# booster.net
KiCad netlist of a schematic drawn in EAGLE
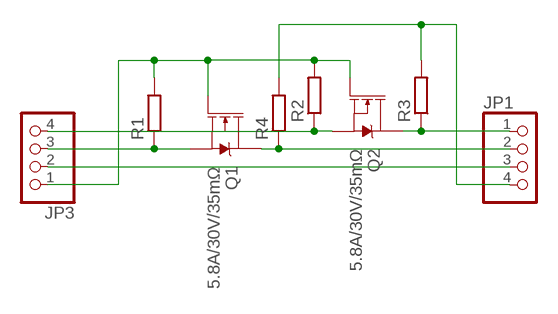
[diagram p0: schematic, sheet 1]

(export (version "E")
  (design (tool "Eeschema 10.0.6"))
  (components
    (comp (ref "JP1")
      (value "PINHD-1X4/90")
      (footprint "eagle-import:1X04_90")
      (libsource (lib "eagle-import") (part "PINHD-1X4/90"))
    )
    (comp (ref "JP3")
      (value "PINHD-1X4/90")
      (footprint "eagle-import:1X04_90")
      (libsource (lib "eagle-import") (part "PINHD-1X4/90"))
    )
    (comp (ref "Q1")
      (value "5.8A/30V/35mΩ")
      (footprint "eagle-import:SOT23-3")
      (libsource (lib "eagle-import") (part "MOSFET-NCH-AO3404A"))
    )
    (comp (ref "Q2")
      (value "5.8A/30V/35mΩ")
      (footprint "eagle-import:SOT23-3")
      (libsource (lib "eagle-import") (part "MOSFET-NCH-AO3404A"))
    )
    (comp (ref "R1")
      (value "R-EU_R0805")
      (footprint "eagle-import:R0805")
      (libsource (lib "eagle-import") (part "R-EU_R0805"))
    )
    (comp (ref "R2")
      (value "R-EU_R0805")
      (footprint "eagle-import:R0805")
      (libsource (lib "eagle-import") (part "R-EU_R0805"))
    )
    (comp (ref "R3")
      (value "R-EU_R0805")
      (footprint "eagle-import:R0805")
      (libsource (lib "eagle-import") (part "R-EU_R0805"))
    )
    (comp (ref "R4")
      (value "R-EU_R0805")
      (footprint "eagle-import:R0805")
      (libsource (lib "eagle-import") (part "R-EU_R0805"))
    )
  )
  (nets
    (net (code "1") (name "Net-(JP1-Pad3)") (class "Default")
      (node (ref "JP1") (pin "3") (pinfunction "3_3") (pintype "passive"))
      (node (ref "JP3") (pin "2") (pinfunction "2_2") (pintype "passive"))
    )
    (net (code "2") (name "Net-(JP1-Pad4)") (class "Default")
      (node (ref "JP1") (pin "4") (pinfunction "4_4") (pintype "passive"))
      (node (ref "R3") (pin "2") (pinfunction "2_2") (pintype "passive"))
      (node (ref "R4") (pin "2") (pinfunction "2_2") (pintype "passive"))
    )
    (net (code "3") (name "Net-(Q1-D)") (class "Default")
      (node (ref "JP1") (pin "2") (pinfunction "2_2") (pintype "passive"))
      (node (ref "Q1") (pin "3") (pinfunction "D_3") (pintype "bidirectional"))
      (node (ref "R4") (pin "1") (pinfunction "1_1") (pintype "passive"))
    )
    (net (code "4") (name "Net-(Q1-G)") (class "Default")
      (node (ref "JP3") (pin "1") (pinfunction "1_1") (pintype "passive"))
      (node (ref "Q1") (pin "1") (pinfunction "G_1") (pintype "bidirectional"))
      (node (ref "Q2") (pin "1") (pinfunction "G_1") (pintype "bidirectional"))
      (node (ref "R1") (pin "2") (pinfunction "2_2") (pintype "passive"))
      (node (ref "R2") (pin "2") (pinfunction "2_2") (pintype "passive"))
    )
    (net (code "5") (name "Net-(Q1-S)") (class "Default")
      (node (ref "JP3") (pin "3") (pinfunction "3_3") (pintype "passive"))
      (node (ref "Q1") (pin "2") (pinfunction "S_2") (pintype "bidirectional"))
      (node (ref "R1") (pin "1") (pinfunction "1_1") (pintype "passive"))
    )
    (net (code "6") (name "Net-(Q2-D)") (class "Default")
      (node (ref "JP1") (pin "1") (pinfunction "1_1") (pintype "passive"))
      (node (ref "Q2") (pin "3") (pinfunction "D_3") (pintype "bidirectional"))
      (node (ref "R3") (pin "1") (pinfunction "1_1") (pintype "passive"))
    )
    (net (code "7") (name "Net-(Q2-S)") (class "Default")
      (node (ref "JP3") (pin "4") (pinfunction "4_4") (pintype "passive"))
      (node (ref "Q2") (pin "2") (pinfunction "S_2") (pintype "bidirectional"))
      (node (ref "R2") (pin "1") (pinfunction "1_1") (pintype "passive"))
    )
  )
)
